# KickerInterface.net
KiCad netlist of a schematic drawn in Altium Designer
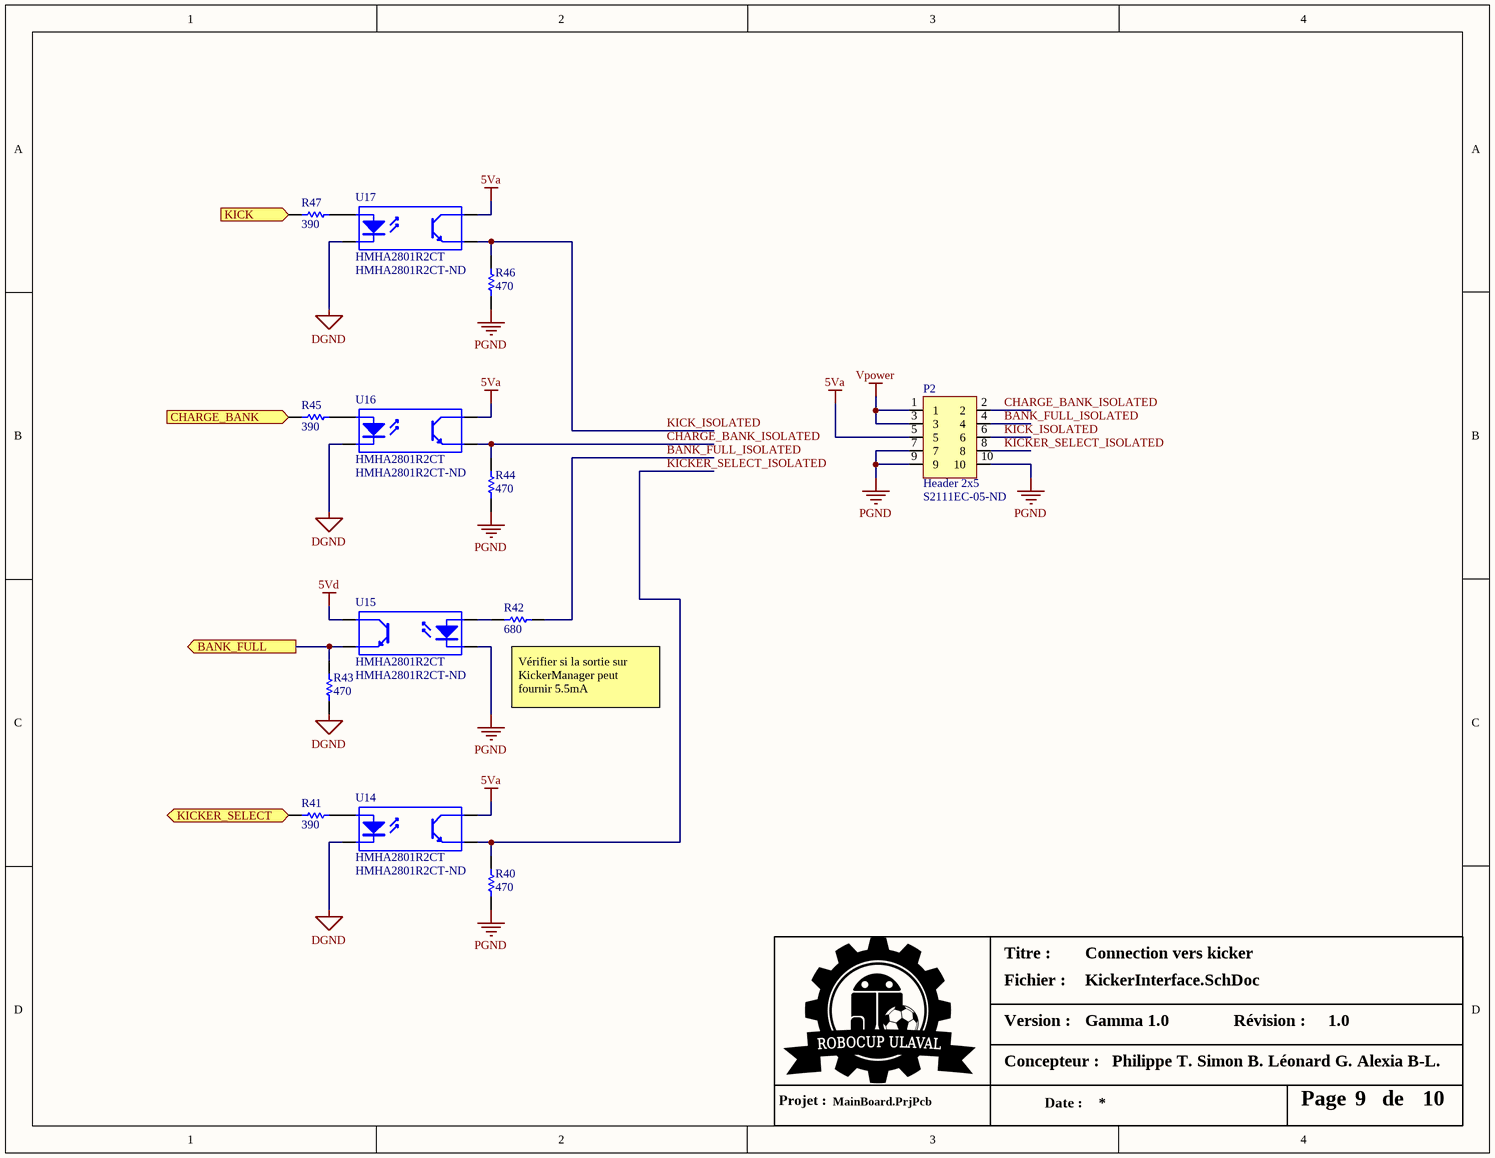
[diagram p0: KickerInterface.SchDoc]

(export (version "E")
  (design (tool "Eeschema 10.0.6"))
  (components
    (comp (ref "P2")
      (value "Header 2x5")
      (footprint "HDR2x5_Right_Angle")
      (description "Header 10pins 2 rows 100mil right angle")
      (fields (field (name "SUPPLIER PART NUMBER 2") "S2111EC-05-ND"))
      (libsource (lib "MainBoard") (part "header 2x5 100mil right angle"))
    )
    (comp (ref "R40")
      (value "RC0603JR-07470RL")
      (footprint "0603")
      (description "RES SMD 470 OHM 5% 1/10W 0603")
      (fields
        (field (name "MANUFACTURER") "Yageo")
        (field (name "TOLERANCE") "±5%")
        (field (name "RESISTANCE (OHMS)") "470")
      )
      (libsource (lib "ResCap") (part "RC0603JR-07470RL"))
    )
    (comp (ref "R41")
      (value "RC0603JR-07390RL")
      (footprint "0603")
      (description "RES SMD 390 OHM 5% 1/10W 0603")
      (fields
        (field (name "MANUFACTURER") "Yageo")
        (field (name "TOLERANCE") "±5%")
        (field (name "RESISTANCE (OHMS)") "390")
      )
      (libsource (lib "ResCap") (part "RC0603JR-07390RL"))
    )
    (comp (ref "R42")
      (value "RC0603JR-07680RL")
      (footprint "0603")
      (description "RES SMD 680 OHM 5% 1/10W 0603")
      (fields
        (field (name "MANUFACTURER") "Yageo")
        (field (name "TOLERANCE") "±5%")
        (field (name "RESISTANCE (OHMS)") "680")
      )
      (libsource (lib "ResCap") (part "RC0603JR-07680RL"))
    )
    (comp (ref "R43")
      (value "RC0603JR-07470RL")
      (footprint "0603")
      (description "RES SMD 470 OHM 5% 1/10W 0603")
      (fields
        (field (name "MANUFACTURER") "Yageo")
        (field (name "TOLERANCE") "±5%")
        (field (name "RESISTANCE (OHMS)") "470")
      )
      (libsource (lib "ResCap") (part "RC0603JR-07470RL"))
    )
    (comp (ref "R44")
      (value "RC0603JR-07470RL")
      (footprint "0603")
      (description "RES SMD 470 OHM 5% 1/10W 0603")
      (fields
        (field (name "MANUFACTURER") "Yageo")
        (field (name "TOLERANCE") "±5%")
        (field (name "RESISTANCE (OHMS)") "470")
      )
      (libsource (lib "ResCap") (part "RC0603JR-07470RL"))
    )
    (comp (ref "R45")
      (value "RC0603JR-07390RL")
      (footprint "0603")
      (description "RES SMD 390 OHM 5% 1/10W 0603")
      (fields
        (field (name "MANUFACTURER") "Yageo")
        (field (name "TOLERANCE") "±5%")
        (field (name "RESISTANCE (OHMS)") "390")
      )
      (libsource (lib "ResCap") (part "RC0603JR-07390RL"))
    )
    (comp (ref "R46")
      (value "RC0603JR-07470RL")
      (footprint "0603")
      (description "RES SMD 470 OHM 5% 1/10W 0603")
      (fields
        (field (name "MANUFACTURER") "Yageo")
        (field (name "TOLERANCE") "±5%")
        (field (name "RESISTANCE (OHMS)") "470")
      )
      (libsource (lib "ResCap") (part "RC0603JR-07470RL"))
    )
    (comp (ref "R47")
      (value "RC0603JR-07390RL")
      (footprint "0603")
      (description "RES SMD 390 OHM 5% 1/10W 0603")
      (fields
        (field (name "MANUFACTURER") "Yageo")
        (field (name "TOLERANCE") "±5%")
        (field (name "RESISTANCE (OHMS)") "390")
      )
      (libsource (lib "ResCap") (part "RC0603JR-07390RL"))
    )
    (comp (ref "U14")
      (value "HMHA2801R2CT")
      (footprint "SOIC127P700X220-4N")
      (description "OPTOISOLATOR 3.75KV TRANS 4-SO")
      (fields (field (name "SUPPLIER PART NUMBER 1") "HMHA2801R2CT-ND"))
      (libsource (lib "MainBoard") (part "HMHA2801R2CT"))
    )
    (comp (ref "U15")
      (value "HMHA2801R2CT")
      (footprint "SOIC127P700X220-4N")
      (description "OPTOISOLATOR 3.75KV TRANS 4-SO")
      (fields (field (name "SUPPLIER PART NUMBER 1") "HMHA2801R2CT-ND"))
      (libsource (lib "MainBoard") (part "HMHA2801R2CT"))
    )
    (comp (ref "U16")
      (value "HMHA2801R2CT")
      (footprint "SOIC127P700X220-4N")
      (description "OPTOISOLATOR 3.75KV TRANS 4-SO")
      (fields (field (name "SUPPLIER PART NUMBER 1") "HMHA2801R2CT-ND"))
      (libsource (lib "MainBoard") (part "HMHA2801R2CT"))
    )
    (comp (ref "U17")
      (value "HMHA2801R2CT")
      (footprint "SOIC127P700X220-4N")
      (description "OPTOISOLATOR 3.75KV TRANS 4-SO")
      (fields (field (name "SUPPLIER PART NUMBER 1") "HMHA2801R2CT-ND"))
      (libsource (lib "MainBoard") (part "HMHA2801R2CT"))
    )
  )
  (nets
    (net (code "1") (name "/BANK_FULL") (class "Default")
      (node (ref "R43") (pin "2") (pinfunction "2_2") (pintype "passive"))
      (node (ref "U15") (pin "3") (pinfunction "E_3") (pintype "passive"))
    )
    (net (code "2") (name "/BANK_FULL_ISOLATED") (class "Default")
      (node (ref "P2") (pin "4") (pinfunction "4_4") (pintype "passive"))
      (node (ref "R42") (pin "2") (pinfunction "2_2") (pintype "passive"))
    )
    (net (code "3") (name "/CHARGE_BANK") (class "Default")
      (node (ref "R45") (pin "1") (pinfunction "1_1") (pintype "passive"))
    )
    (net (code "4") (name "/CHARGE_BANK_ISOLATED") (class "Default")
      (node (ref "P2") (pin "2") (pinfunction "2_2") (pintype "passive"))
      (node (ref "R44") (pin "2") (pinfunction "2_2") (pintype "passive"))
      (node (ref "U16") (pin "3") (pinfunction "E_3") (pintype "passive"))
    )
    (net (code "5") (name "/KICK") (class "Default")
      (node (ref "R47") (pin "1") (pinfunction "1_1") (pintype "passive"))
    )
    (net (code "6") (name "/KICKER_SELECT") (class "Default")
      (node (ref "R41") (pin "1") (pinfunction "1_1") (pintype "passive"))
    )
    (net (code "7") (name "/KICKER_SELECT_ISOLATED") (class "Default")
      (node (ref "P2") (pin "8") (pinfunction "8_8") (pintype "passive"))
      (node (ref "R40") (pin "2") (pinfunction "2_2") (pintype "passive"))
      (node (ref "U14") (pin "3") (pinfunction "E_3") (pintype "passive"))
    )
    (net (code "8") (name "/KICK_ISOLATED") (class "Default")
      (node (ref "P2") (pin "6") (pinfunction "6_6") (pintype "passive"))
      (node (ref "R46") (pin "2") (pinfunction "2_2") (pintype "passive"))
      (node (ref "U17") (pin "3") (pinfunction "E_3") (pintype "passive"))
    )
    (net (code "9") (name "5Va") (class "Default")
      (node (ref "P2") (pin "5") (pinfunction "5_5") (pintype "passive"))
      (node (ref "U14") (pin "4") (pinfunction "C_4") (pintype "passive"))
      (node (ref "U16") (pin "4") (pinfunction "C_4") (pintype "passive"))
      (node (ref "U17") (pin "4") (pinfunction "C_4") (pintype "passive"))
    )
    (net (code "10") (name "5Vd") (class "Default")
      (node (ref "U15") (pin "4") (pinfunction "C_4") (pintype "passive"))
    )
    (net (code "11") (name "DGND") (class "Default")
      (node (ref "R43") (pin "1") (pinfunction "1_1") (pintype "passive"))
      (node (ref "U14") (pin "2") (pinfunction "K_2") (pintype "passive"))
      (node (ref "U16") (pin "2") (pinfunction "K_2") (pintype "passive"))
      (node (ref "U17") (pin "2") (pinfunction "K_2") (pintype "passive"))
    )
    (net (code "12") (name "Net-(U14-A)") (class "Default")
      (node (ref "R41") (pin "2") (pinfunction "2_2") (pintype "passive"))
      (node (ref "U14") (pin "1") (pinfunction "A_1") (pintype "passive"))
    )
    (net (code "13") (name "Net-(U15-A)") (class "Default")
      (node (ref "R42") (pin "1") (pinfunction "1_1") (pintype "passive"))
      (node (ref "U15") (pin "1") (pinfunction "A_1") (pintype "passive"))
    )
    (net (code "14") (name "Net-(U16-A)") (class "Default")
      (node (ref "R45") (pin "2") (pinfunction "2_2") (pintype "passive"))
      (node (ref "U16") (pin "1") (pinfunction "A_1") (pintype "passive"))
    )
    (net (code "15") (name "Net-(U17-A)") (class "Default")
      (node (ref "R47") (pin "2") (pinfunction "2_2") (pintype "passive"))
      (node (ref "U17") (pin "1") (pinfunction "A_1") (pintype "passive"))
    )
    (net (code "16") (name "PGND") (class "Default")
      (node (ref "P2") (pin "10") (pinfunction "10_10") (pintype "passive"))
      (node (ref "P2") (pin "7") (pinfunction "7_7") (pintype "passive"))
      (node (ref "P2") (pin "9") (pinfunction "9_9") (pintype "passive"))
      (node (ref "R40") (pin "1") (pinfunction "1_1") (pintype "passive"))
      (node (ref "R44") (pin "1") (pinfunction "1_1") (pintype "passive"))
      (node (ref "R46") (pin "1") (pinfunction "1_1") (pintype "passive"))
      (node (ref "U15") (pin "2") (pinfunction "K_2") (pintype "passive"))
    )
    (net (code "17") (name "Vpower") (class "Default")
      (node (ref "P2") (pin "1") (pinfunction "1_1") (pintype "passive"))
      (node (ref "P2") (pin "3") (pinfunction "3_3") (pintype "passive"))
    )
  )
)
